# attiny85_LCD_rotaryenc_w_btn.net
KiCad netlist of a schematic drawn in EAGLE
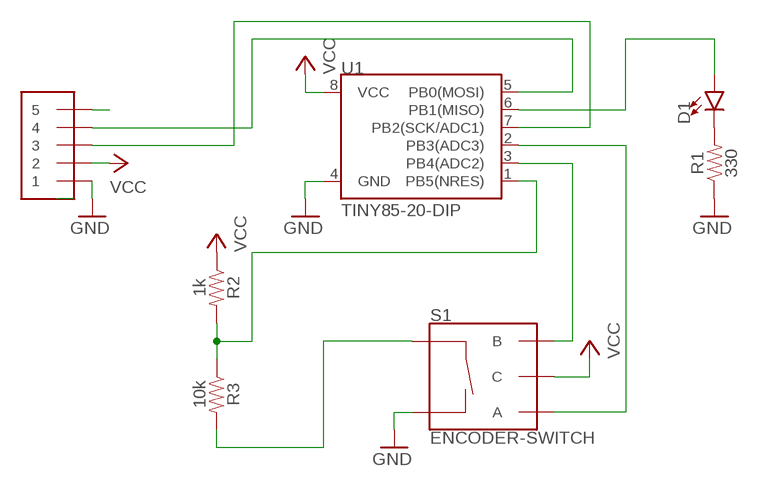
[diagram p0: schematic, sheet 1]

(export (version "E")
  (design (tool "Eeschema 10.0.6"))
  (components
    (comp (ref "D1")
      (value "LED3MM")
      (footprint "eagle-import:LED_3MM")
      (libsource (lib "eagle-import") (part "LED3MM"))
    )
    (comp (ref "J1")
      (value "1X5")
      (footprint "eagle-import:3.5MM-5P")
      (libsource (lib "eagle-import") (part "1X5"))
    )
    (comp (ref "R1")
      (value "330")
      (footprint "eagle-import:AXIAL-0.3")
      (libsource (lib "eagle-import") (part "330OHM-HORIZ-1/10W-5%"))
    )
    (comp (ref "R2")
      (value "1k")
      (footprint "eagle-import:AXIAL-0.3")
      (libsource (lib "eagle-import") (part "1KOHM-HORIZ-1/4W-5%"))
    )
    (comp (ref "R3")
      (value "10k")
      (footprint "eagle-import:AXIAL-0.3")
      (libsource (lib "eagle-import") (part "10KOHM-HORIZ-1/6W-5%"))
    )
    (comp (ref "S1")
      (value "ENCODER-SWITCH")
      (footprint "eagle-import:ROTARY_ENC_PLAIN")
      (libsource (lib "eagle-import") (part "ENCODER-SWITCH"))
    )
    (comp (ref "U1")
      (value "TINY85-20-DIP")
      (footprint "eagle-import:DIP08_MCU")
      (libsource (lib "eagle-import") (part "ATTINY45TINY85-20-DIP"))
    )
  )
  (nets
    (net (code "1") (name "GND") (class "Default")
      (node (ref "J1") (pin "1") (pinfunction "1_1") (pintype "passive"))
      (node (ref "R1") (pin "P$1") (pinfunction "1_P$1") (pintype "passive"))
      (node (ref "S1") (pin "SW-") (pinfunction "SW-_SW-") (pintype "bidirectional"))
      (node (ref "U1") (pin "4") (pinfunction "GND_4") (pintype "bidirectional"))
    )
    (net (code "2") (name "Net-(D1-C)") (class "Default")
      (node (ref "D1") (pin "K") (pinfunction "C_K") (pintype "passive"))
      (node (ref "R1") (pin "P$2") (pinfunction "2_P$2") (pintype "passive"))
    )
    (net (code "3") (name "Net-(R2-2)") (class "Default")
      (node (ref "R2") (pin "P$2") (pinfunction "2_P$2") (pintype "passive"))
      (node (ref "R3") (pin "P$1") (pinfunction "1_P$1") (pintype "passive"))
      (node (ref "U1") (pin "1") (pinfunction "PB5(NRES)_1") (pintype "bidirectional"))
    )
    (net (code "4") (name "Net-(R3-2)") (class "Default")
      (node (ref "R3") (pin "P$2") (pinfunction "2_P$2") (pintype "passive"))
      (node (ref "S1") (pin "SW+") (pinfunction "SW+_SW+") (pintype "bidirectional"))
    )
    (net (code "5") (name "Net-(U1-PB0(MOSI))") (class "Default")
      (node (ref "J1") (pin "4") (pinfunction "4_4") (pintype "passive"))
      (node (ref "U1") (pin "5") (pinfunction "PB0(MOSI)_5") (pintype "bidirectional"))
    )
    (net (code "6") (name "Net-(U1-PB1(MISO))") (class "Default")
      (node (ref "D1") (pin "A") (pinfunction "A_A") (pintype "passive"))
      (node (ref "U1") (pin "6") (pinfunction "PB1(MISO)_6") (pintype "bidirectional"))
    )
    (net (code "7") (name "Net-(U1-PB2(SCK{slash}ADC1))") (class "Default")
      (node (ref "J1") (pin "3") (pinfunction "3_3") (pintype "passive"))
      (node (ref "U1") (pin "7") (pinfunction "PB2(SCK/ADC1)_7") (pintype "bidirectional"))
    )
    (net (code "8") (name "Net-(U1-PB3(ADC3))") (class "Default")
      (node (ref "S1") (pin "A") (pinfunction "A_A") (pintype "bidirectional"))
      (node (ref "U1") (pin "2") (pinfunction "PB3(ADC3)_2") (pintype "bidirectional"))
    )
    (net (code "9") (name "Net-(U1-PB4(ADC2))") (class "Default")
      (node (ref "S1") (pin "B") (pinfunction "B_B") (pintype "bidirectional"))
      (node (ref "U1") (pin "3") (pinfunction "PB4(ADC2)_3") (pintype "bidirectional"))
    )
    (net (code "10") (name "VCC") (class "Default")
      (node (ref "J1") (pin "2") (pinfunction "2_2") (pintype "passive"))
      (node (ref "R2") (pin "P$1") (pinfunction "1_P$1") (pintype "passive"))
      (node (ref "S1") (pin "C") (pinfunction "C_C") (pintype "bidirectional"))
      (node (ref "U1") (pin "8") (pinfunction "VCC_8") (pintype "bidirectional"))
    )
    (net (code "11") (name "unconnected-(J1-Pad5)") (class "Default")
      (node (ref "J1") (pin "5") (pinfunction "5_5") (pintype "passive"))
    )
  )
)
